# LeaversDinner_invite_Sch.net
KiCad netlist of a schematic drawn in Altium Designer
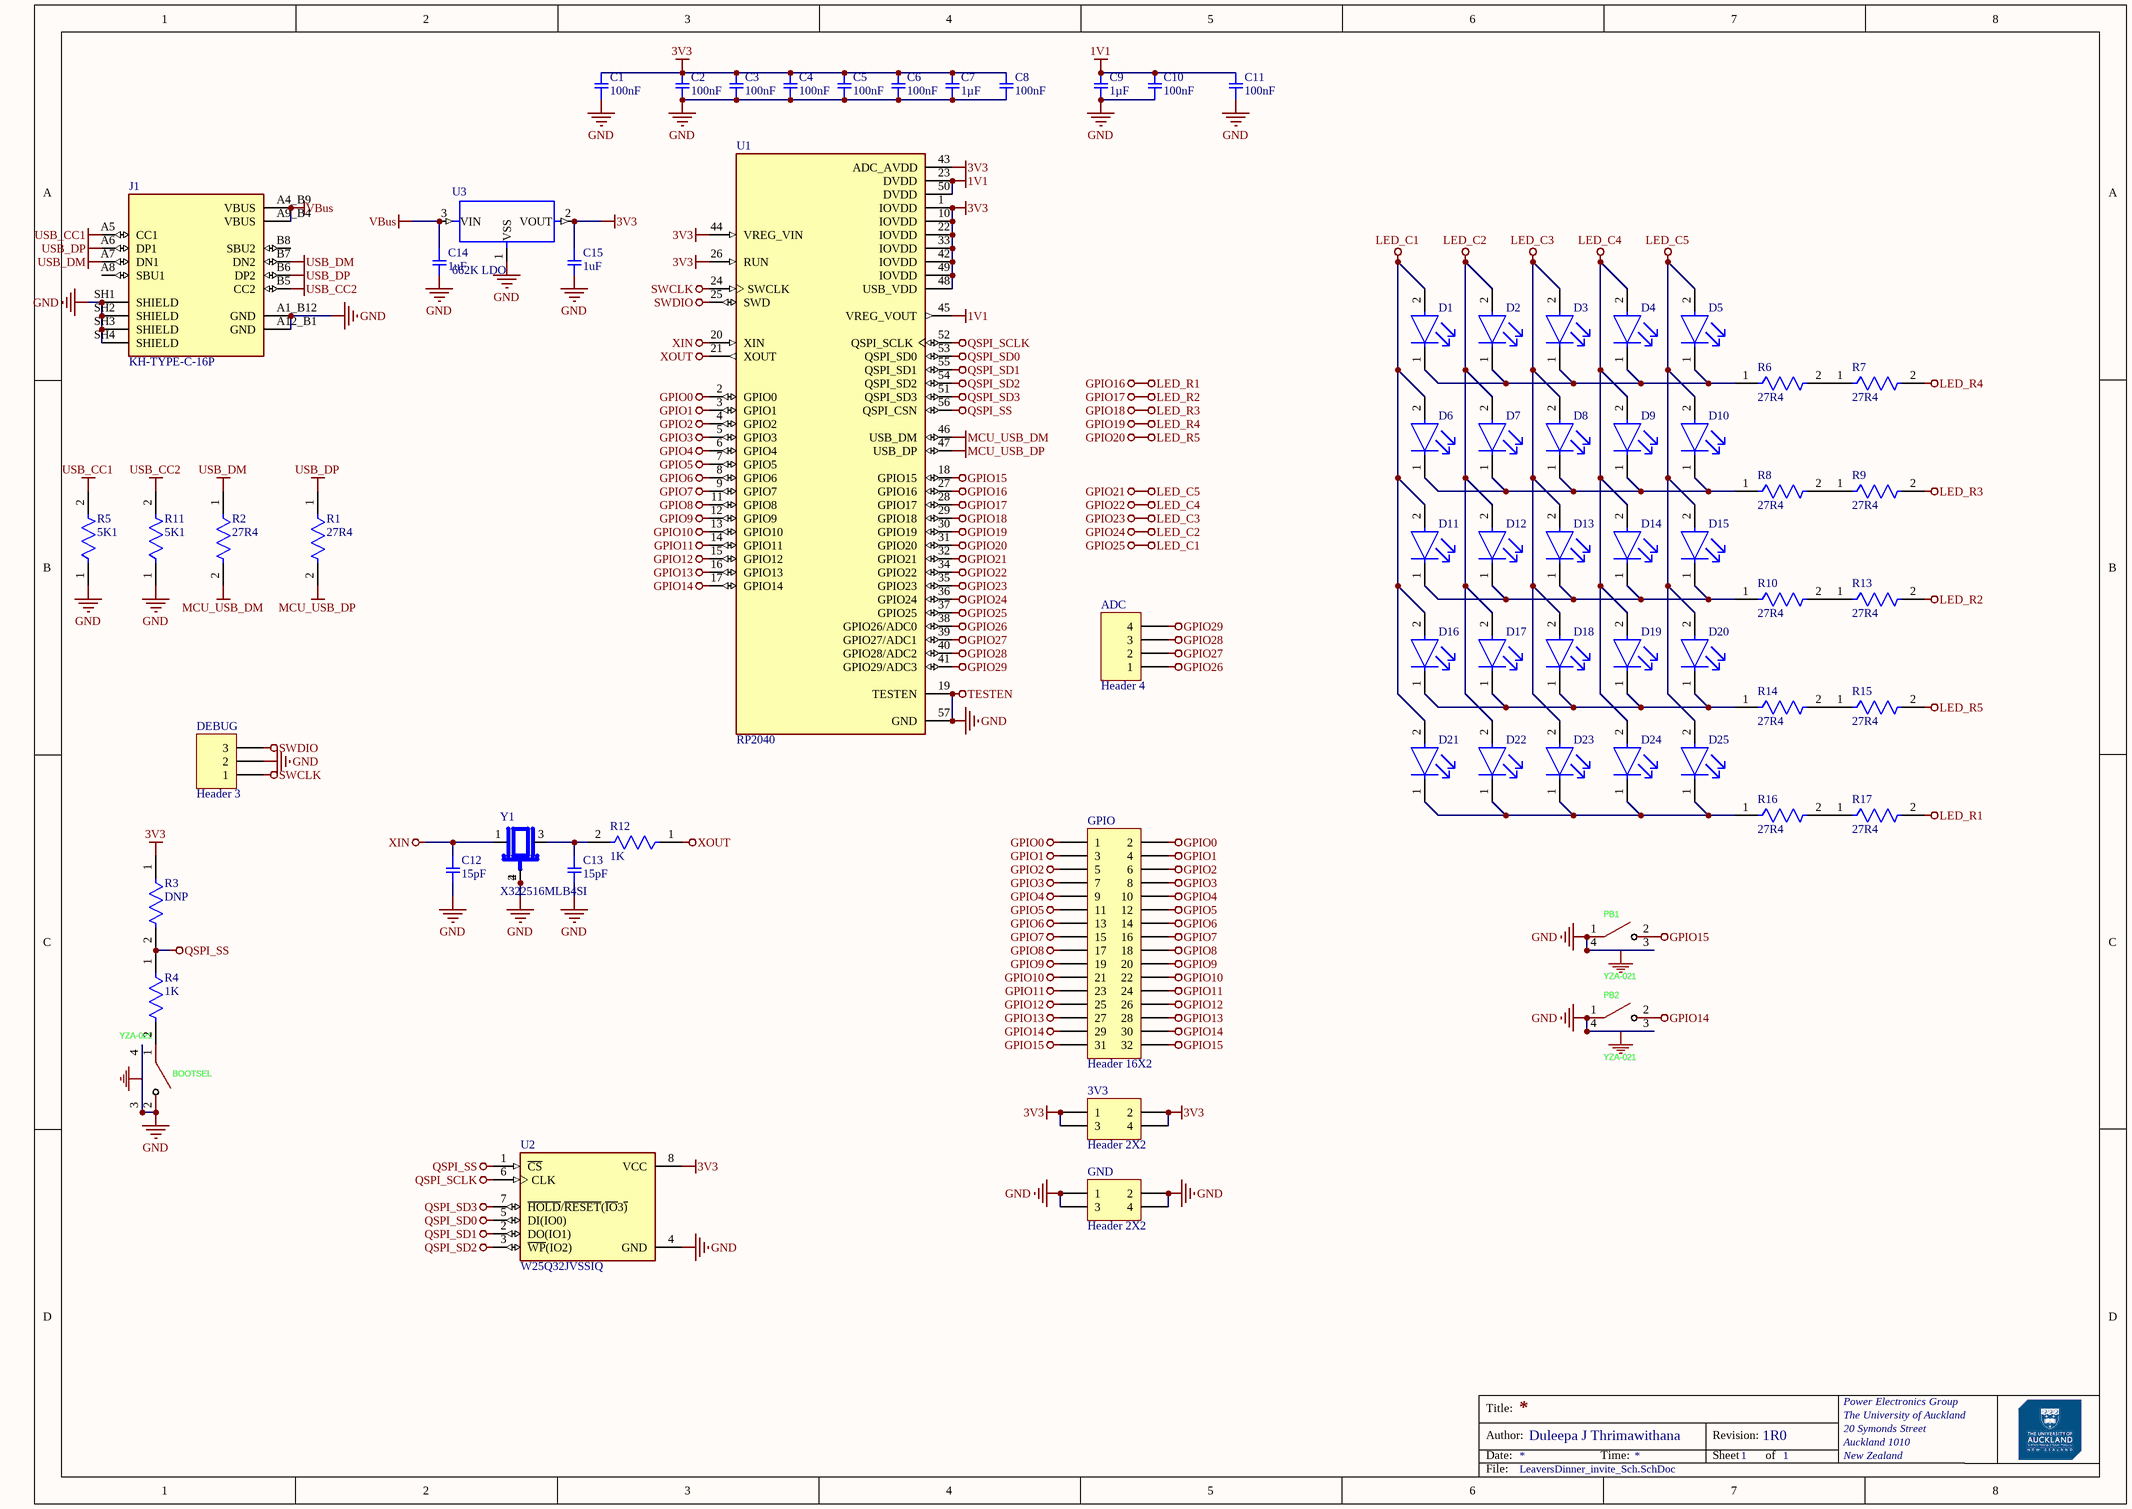
[diagram p0: LeaversDinner_invite_Sch.SchDoc]

(export (version "E")
  (design (tool "Eeschema 10.0.6"))
  (components
    (comp (ref "3V3")
      (value "Header 2X2")
      (footprint "HDR2X2")
      (description "Header, 2-Pin, Dual row")
      (fields (field (name "PUBLISHER") "Altium Limited"))
      (libsource (lib "Miscellaneous Connectors") (part "Header 2X2"))
    )
    (comp (ref "ADC")
      (value "Header 4")
      (footprint "HDR1X4")
      (description "Header, 4-Pin")
      (fields (field (name "PUBLISHER") "Altium Limited"))
      (libsource (lib "Miscellaneous Connectors") (part "Header 4"))
    )
    (comp (ref "BOOTSEL")
      (value "YZA-021")
      (footprint "SW-SMD_YZA-021")
      (fields (field (name "MANUFACTURER") "YIZHI(逸致)"))
      (libsource (lib "YZA-021") (part "YZA-021"))
    )
    (comp (ref "C1")
      (value "100nF")
      (footprint "SMD-0402C")
      (description "CAP CER 1UF 10V X7S 0402")
      (fields
        (field (name "DIGI-KEY PART NUMBER") "490-13409-1-ND")
        (field (name "PART NUMBER") "GCM155C71A105KE38D")
      )
      (libsource (lib "capacitor_murata_0402") (part "GCM155C71A105KE38D"))
    )
    (comp (ref "C2")
      (value "100nF")
      (footprint "SMD-0402C")
      (description "CAP CER 1UF 10V X7S 0402")
      (fields
        (field (name "DIGI-KEY PART NUMBER") "490-13409-1-ND")
        (field (name "PART NUMBER") "GCM155C71A105KE38D")
      )
      (libsource (lib "capacitor_murata_0402") (part "GCM155C71A105KE38D"))
    )
    (comp (ref "C3")
      (value "100nF")
      (footprint "SMD-0402C")
      (description "CAP CER 1UF 10V X7S 0402")
      (fields
        (field (name "DIGI-KEY PART NUMBER") "490-13409-1-ND")
        (field (name "PART NUMBER") "GCM155C71A105KE38D")
      )
      (libsource (lib "capacitor_murata_0402") (part "GCM155C71A105KE38D"))
    )
    (comp (ref "C4")
      (value "100nF")
      (footprint "SMD-0402C")
      (description "CAP CER 1UF 10V X7S 0402")
      (fields
        (field (name "DIGI-KEY PART NUMBER") "490-13409-1-ND")
        (field (name "PART NUMBER") "GCM155C71A105KE38D")
      )
      (libsource (lib "capacitor_murata_0402") (part "GCM155C71A105KE38D"))
    )
    (comp (ref "C5")
      (value "100nF")
      (footprint "SMD-0402C")
      (description "CAP CER 1UF 10V X7S 0402")
      (fields
        (field (name "DIGI-KEY PART NUMBER") "490-13409-1-ND")
        (field (name "PART NUMBER") "GCM155C71A105KE38D")
      )
      (libsource (lib "capacitor_murata_0402") (part "GCM155C71A105KE38D"))
    )
    (comp (ref "C6")
      (value "100nF")
      (footprint "SMD-0402C")
      (description "CAP CER 1UF 10V X7S 0402")
      (fields
        (field (name "DIGI-KEY PART NUMBER") "490-13409-1-ND")
        (field (name "PART NUMBER") "GCM155C71A105KE38D")
      )
      (libsource (lib "capacitor_murata_0402") (part "GCM155C71A105KE38D"))
    )
    (comp (ref "C7")
      (value "1µF")
      (footprint "SMD-0402C")
      (description "CAP CER 1UF 10V X7S 0402")
      (fields
        (field (name "DIGI-KEY PART NUMBER") "490-13409-1-ND")
        (field (name "PART NUMBER") "GCM155C71A105KE38D")
      )
      (libsource (lib "capacitor_murata_0402") (part "GCM155C71A105KE38D"))
    )
    (comp (ref "C8")
      (value "100nF")
      (footprint "SMD-0402C")
      (description "CAP CER 1UF 10V X7S 0402")
      (fields
        (field (name "DIGI-KEY PART NUMBER") "490-13409-1-ND")
        (field (name "PART NUMBER") "GCM155C71A105KE38D")
      )
      (libsource (lib "capacitor_murata_0402") (part "GCM155C71A105KE38D"))
    )
    (comp (ref "C9")
      (value "1µF")
      (footprint "SMD-0402C")
      (description "CAP CER 1UF 10V X7S 0402")
      (fields
        (field (name "DIGI-KEY PART NUMBER") "490-13409-1-ND")
        (field (name "PART NUMBER") "GCM155C71A105KE38D")
      )
      (libsource (lib "capacitor_murata_0402") (part "GCM155C71A105KE38D"))
    )
    (comp (ref "C10")
      (value "100nF")
      (footprint "SMD-0402C")
      (description "CAP CER 1UF 10V X7S 0402")
      (fields
        (field (name "DIGI-KEY PART NUMBER") "490-13409-1-ND")
        (field (name "PART NUMBER") "GCM155C71A105KE38D")
      )
      (libsource (lib "capacitor_murata_0402") (part "GCM155C71A105KE38D"))
    )
    (comp (ref "C11")
      (value "100nF")
      (footprint "SMD-0402C")
      (description "CAP CER 1UF 10V X7S 0402")
      (fields
        (field (name "DIGI-KEY PART NUMBER") "490-13409-1-ND")
        (field (name "PART NUMBER") "GCM155C71A105KE38D")
      )
      (libsource (lib "capacitor_murata_0402") (part "GCM155C71A105KE38D"))
    )
    (comp (ref "C12")
      (value "15pF")
      (footprint "SMD-0402C")
      (description "CAP CER 1UF 10V X7S 0402")
      (fields
        (field (name "DIGI-KEY PART NUMBER") "490-13409-1-ND")
        (field (name "PART NUMBER") "GCM155C71A105KE38D")
      )
      (libsource (lib "capacitor_murata_0402") (part "GCM155C71A105KE38D"))
    )
    (comp (ref "C13")
      (value "15pF")
      (footprint "SMD-0402C")
      (description "CAP CER 1UF 10V X7S 0402")
      (fields
        (field (name "DIGI-KEY PART NUMBER") "490-13409-1-ND")
        (field (name "PART NUMBER") "GCM155C71A105KE38D")
      )
      (libsource (lib "capacitor_murata_0402") (part "GCM155C71A105KE38D"))
    )
    (comp (ref "C14")
      (value "1uF")
      (footprint "SMD-0402C")
      (description "CAP CER 1UF 10V X7S 0402")
      (fields
        (field (name "DIGI-KEY PART NUMBER") "490-13409-1-ND")
        (field (name "PART NUMBER") "GCM155C71A105KE38D")
      )
      (libsource (lib "capacitor_murata_0402") (part "GCM155C71A105KE38D"))
    )
    (comp (ref "C15")
      (value "1uF")
      (footprint "SMD-0402C")
      (description "CAP CER 1UF 10V X7S 0402")
      (fields
        (field (name "DIGI-KEY PART NUMBER") "490-13409-1-ND")
        (field (name "PART NUMBER") "GCM155C71A105KE38D")
      )
      (libsource (lib "capacitor_murata_0402") (part "GCM155C71A105KE38D"))
    )
    (comp (ref "D1")
      (value "VLMW1300-GS08")
      (footprint "FP-6_541-5091_01-4-MFG")
      (description "LED COOL WHITE 0603 SMD")
      (fields
        (field (name "MANUFACTURER") "Vishay")
        (field (name "OCTOPART") "https://octopart.com/vlmw1300-gs08-vishay-21709203")
      )
      (libsource (lib "Altium Content Vault") (part "8706943c75ba83719d021d2fdc84c58"))
    )
    (comp (ref "D2")
      (value "VLMW1300-GS08")
      (footprint "FP-6_541-5091_01-4-MFG")
      (description "LED COOL WHITE 0603 SMD")
      (fields
        (field (name "MANUFACTURER") "Vishay")
        (field (name "OCTOPART") "https://octopart.com/vlmw1300-gs08-vishay-21709203")
      )
      (libsource (lib "Altium Content Vault") (part "8706943c75ba83719d021d2fdc84c58"))
    )
    (comp (ref "D3")
      (value "VLMW1300-GS08")
      (footprint "FP-6_541-5091_01-4-MFG")
      (description "LED COOL WHITE 0603 SMD")
      (fields
        (field (name "MANUFACTURER") "Vishay")
        (field (name "OCTOPART") "https://octopart.com/vlmw1300-gs08-vishay-21709203")
      )
      (libsource (lib "Altium Content Vault") (part "8706943c75ba83719d021d2fdc84c58"))
    )
    (comp (ref "D4")
      (value "VLMW1300-GS08")
      (footprint "FP-6_541-5091_01-4-MFG")
      (description "LED COOL WHITE 0603 SMD")
      (fields
        (field (name "MANUFACTURER") "Vishay")
        (field (name "OCTOPART") "https://octopart.com/vlmw1300-gs08-vishay-21709203")
      )
      (libsource (lib "Altium Content Vault") (part "8706943c75ba83719d021d2fdc84c58"))
    )
    (comp (ref "D5")
      (value "VLMW1300-GS08")
      (footprint "FP-6_541-5091_01-4-MFG")
      (description "LED COOL WHITE 0603 SMD")
      (fields
        (field (name "MANUFACTURER") "Vishay")
        (field (name "OCTOPART") "https://octopart.com/vlmw1300-gs08-vishay-21709203")
      )
      (libsource (lib "Altium Content Vault") (part "8706943c75ba83719d021d2fdc84c58"))
    )
    (comp (ref "D6")
      (value "VLMW1300-GS08")
      (footprint "FP-6_541-5091_01-4-MFG")
      (description "LED COOL WHITE 0603 SMD")
      (fields
        (field (name "MANUFACTURER") "Vishay")
        (field (name "OCTOPART") "https://octopart.com/vlmw1300-gs08-vishay-21709203")
      )
      (libsource (lib "Altium Content Vault") (part "8706943c75ba83719d021d2fdc84c58"))
    )
    (comp (ref "D7")
      (value "VLMW1300-GS08")
      (footprint "FP-6_541-5091_01-4-MFG")
      (description "LED COOL WHITE 0603 SMD")
      (fields
        (field (name "MANUFACTURER") "Vishay")
        (field (name "OCTOPART") "https://octopart.com/vlmw1300-gs08-vishay-21709203")
      )
      (libsource (lib "Altium Content Vault") (part "8706943c75ba83719d021d2fdc84c58"))
    )
    (comp (ref "D8")
      (value "VLMW1300-GS08")
      (footprint "FP-6_541-5091_01-4-MFG")
      (description "LED COOL WHITE 0603 SMD")
      (fields
        (field (name "MANUFACTURER") "Vishay")
        (field (name "OCTOPART") "https://octopart.com/vlmw1300-gs08-vishay-21709203")
      )
      (libsource (lib "Altium Content Vault") (part "8706943c75ba83719d021d2fdc84c58"))
    )
    (comp (ref "D9")
      (value "VLMW1300-GS08")
      (footprint "FP-6_541-5091_01-4-MFG")
      (description "LED COOL WHITE 0603 SMD")
      (fields
        (field (name "MANUFACTURER") "Vishay")
        (field (name "OCTOPART") "https://octopart.com/vlmw1300-gs08-vishay-21709203")
      )
      (libsource (lib "Altium Content Vault") (part "8706943c75ba83719d021d2fdc84c58"))
    )
    (comp (ref "D10")
      (value "VLMW1300-GS08")
      (footprint "FP-6_541-5091_01-4-MFG")
      (description "LED COOL WHITE 0603 SMD")
      (fields
        (field (name "MANUFACTURER") "Vishay")
        (field (name "OCTOPART") "https://octopart.com/vlmw1300-gs08-vishay-21709203")
      )
      (libsource (lib "Altium Content Vault") (part "8706943c75ba83719d021d2fdc84c58"))
    )
    (comp (ref "D11")
      (value "VLMW1300-GS08")
      (footprint "FP-6_541-5091_01-4-MFG")
      (description "LED COOL WHITE 0603 SMD")
      (fields
        (field (name "MANUFACTURER") "Vishay")
        (field (name "OCTOPART") "https://octopart.com/vlmw1300-gs08-vishay-21709203")
      )
      (libsource (lib "Altium Content Vault") (part "8706943c75ba83719d021d2fdc84c58"))
    )
    (comp (ref "D12")
      (value "VLMW1300-GS08")
      (footprint "FP-6_541-5091_01-4-MFG")
      (description "LED COOL WHITE 0603 SMD")
      (fields
        (field (name "MANUFACTURER") "Vishay")
        (field (name "OCTOPART") "https://octopart.com/vlmw1300-gs08-vishay-21709203")
      )
      (libsource (lib "Altium Content Vault") (part "8706943c75ba83719d021d2fdc84c58"))
    )
    (comp (ref "D13")
      (value "VLMW1300-GS08")
      (footprint "FP-6_541-5091_01-4-MFG")
      (description "LED COOL WHITE 0603 SMD")
      (fields
        (field (name "MANUFACTURER") "Vishay")
        (field (name "OCTOPART") "https://octopart.com/vlmw1300-gs08-vishay-21709203")
      )
      (libsource (lib "Altium Content Vault") (part "8706943c75ba83719d021d2fdc84c58"))
    )
    (comp (ref "D14")
      (value "VLMW1300-GS08")
      (footprint "FP-6_541-5091_01-4-MFG")
      (description "LED COOL WHITE 0603 SMD")
      (fields
        (field (name "MANUFACTURER") "Vishay")
        (field (name "OCTOPART") "https://octopart.com/vlmw1300-gs08-vishay-21709203")
      )
      (libsource (lib "Altium Content Vault") (part "8706943c75ba83719d021d2fdc84c58"))
    )
    (comp (ref "D15")
      (value "VLMW1300-GS08")
      (footprint "FP-6_541-5091_01-4-MFG")
      (description "LED COOL WHITE 0603 SMD")
      (fields
        (field (name "MANUFACTURER") "Vishay")
        (field (name "OCTOPART") "https://octopart.com/vlmw1300-gs08-vishay-21709203")
      )
      (libsource (lib "Altium Content Vault") (part "8706943c75ba83719d021d2fdc84c58"))
    )
    (comp (ref "D16")
      (value "VLMW1300-GS08")
      (footprint "FP-6_541-5091_01-4-MFG")
      (description "LED COOL WHITE 0603 SMD")
      (fields
        (field (name "MANUFACTURER") "Vishay")
        (field (name "OCTOPART") "https://octopart.com/vlmw1300-gs08-vishay-21709203")
      )
      (libsource (lib "Altium Content Vault") (part "8706943c75ba83719d021d2fdc84c58"))
    )
    (comp (ref "D17")
      (value "VLMW1300-GS08")
      (footprint "FP-6_541-5091_01-4-MFG")
      (description "LED COOL WHITE 0603 SMD")
      (fields
        (field (name "MANUFACTURER") "Vishay")
        (field (name "OCTOPART") "https://octopart.com/vlmw1300-gs08-vishay-21709203")
      )
      (libsource (lib "Altium Content Vault") (part "8706943c75ba83719d021d2fdc84c58"))
    )
    (comp (ref "D18")
      (value "VLMW1300-GS08")
      (footprint "FP-6_541-5091_01-4-MFG")
      (description "LED COOL WHITE 0603 SMD")
      (fields
        (field (name "MANUFACTURER") "Vishay")
        (field (name "OCTOPART") "https://octopart.com/vlmw1300-gs08-vishay-21709203")
      )
      (libsource (lib "Altium Content Vault") (part "8706943c75ba83719d021d2fdc84c58"))
    )
    (comp (ref "D19")
      (value "VLMW1300-GS08")
      (footprint "FP-6_541-5091_01-4-MFG")
      (description "LED COOL WHITE 0603 SMD")
      (fields
        (field (name "MANUFACTURER") "Vishay")
        (field (name "OCTOPART") "https://octopart.com/vlmw1300-gs08-vishay-21709203")
      )
      (libsource (lib "Altium Content Vault") (part "8706943c75ba83719d021d2fdc84c58"))
    )
    (comp (ref "D20")
      (value "VLMW1300-GS08")
      (footprint "FP-6_541-5091_01-4-MFG")
      (description "LED COOL WHITE 0603 SMD")
      (fields
        (field (name "MANUFACTURER") "Vishay")
        (field (name "OCTOPART") "https://octopart.com/vlmw1300-gs08-vishay-21709203")
      )
      (libsource (lib "Altium Content Vault") (part "8706943c75ba83719d021d2fdc84c58"))
    )
    (comp (ref "D21")
      (value "VLMW1300-GS08")
      (footprint "FP-6_541-5091_01-4-MFG")
      (description "LED COOL WHITE 0603 SMD")
      (fields
        (field (name "MANUFACTURER") "Vishay")
        (field (name "OCTOPART") "https://octopart.com/vlmw1300-gs08-vishay-21709203")
      )
      (libsource (lib "Altium Content Vault") (part "8706943c75ba83719d021d2fdc84c58"))
    )
    (comp (ref "D22")
      (value "VLMW1300-GS08")
      (footprint "FP-6_541-5091_01-4-MFG")
      (description "LED COOL WHITE 0603 SMD")
      (fields
        (field (name "MANUFACTURER") "Vishay")
        (field (name "OCTOPART") "https://octopart.com/vlmw1300-gs08-vishay-21709203")
      )
      (libsource (lib "Altium Content Vault") (part "8706943c75ba83719d021d2fdc84c58"))
    )
    (comp (ref "D23")
      (value "VLMW1300-GS08")
      (footprint "FP-6_541-5091_01-4-MFG")
      (description "LED COOL WHITE 0603 SMD")
      (fields
        (field (name "MANUFACTURER") "Vishay")
        (field (name "OCTOPART") "https://octopart.com/vlmw1300-gs08-vishay-21709203")
      )
      (libsource (lib "Altium Content Vault") (part "8706943c75ba83719d021d2fdc84c58"))
    )
    (comp (ref "D24")
      (value "VLMW1300-GS08")
      (footprint "FP-6_541-5091_01-4-MFG")
      (description "LED COOL WHITE 0603 SMD")
      (fields
        (field (name "MANUFACTURER") "Vishay")
        (field (name "OCTOPART") "https://octopart.com/vlmw1300-gs08-vishay-21709203")
      )
      (libsource (lib "Altium Content Vault") (part "8706943c75ba83719d021d2fdc84c58"))
    )
    (comp (ref "D25")
      (value "VLMW1300-GS08")
      (footprint "FP-6_541-5091_01-4-MFG")
      (description "LED COOL WHITE 0603 SMD")
      (fields
        (field (name "MANUFACTURER") "Vishay")
        (field (name "OCTOPART") "https://octopart.com/vlmw1300-gs08-vishay-21709203")
      )
      (libsource (lib "Altium Content Vault") (part "8706943c75ba83719d021d2fdc84c58"))
    )
    (comp (ref "DEBUG")
      (value "Header 3")
      (footprint "HDR1X3")
      (description "Header, 3-Pin")
      (fields (field (name "PUBLISHER") "Altium Limited"))
      (libsource (lib "Miscellaneous Connectors") (part "Header 3"))
    )
    (comp (ref "GND")
      (value "Header 2X2")
      (footprint "HDR2X2")
      (description "Header, 2-Pin, Dual row")
      (fields (field (name "PUBLISHER") "Altium Limited"))
      (libsource (lib "Miscellaneous Connectors") (part "Header 2X2"))
    )
    (comp (ref "GPIO")
      (value "Header 16X2")
      (footprint "HDR2X16")
      (description "Header, 16-Pin, Dual row")
      (fields (field (name "PUBLISHER") "Altium Limited"))
      (libsource (lib "Miscellaneous Connectors") (part "Header 16X2"))
    )
    (comp (ref "J1")
      (value "KH-TYPE-C-16P")
      (footprint "KINGHELM_KH-TYPE-C-16P")
      (fields (field (name "MF") "kinghelm"))
      (libsource (lib "KH-TYPE-C-16P") (part "KH-TYPE-C-16P"))
    )
    (comp (ref "PB1")
      (value "YZA-021")
      (footprint "SW-SMD_YZA-021")
      (fields (field (name "MANUFACTURER") "YIZHI(逸致)"))
      (libsource (lib "YZA-021") (part "YZA-021"))
    )
    (comp (ref "PB2")
      (value "YZA-021")
      (footprint "SW-SMD_YZA-021")
      (fields (field (name "MANUFACTURER") "YIZHI(逸致)"))
      (libsource (lib "YZA-021") (part "YZA-021"))
    )
    (comp (ref "R1")
      (value "27R4")
      (footprint "FP-MCR01-IPC_B")
      (description "Thick Film Chip Resistor, 0402, 10MΩ, 5%, 200ppm/°C, 0.063W, 50V")
      (fields (field (name "TOLERANCE") "5%"))
      (libsource (lib "Altium Content Vault") (part "1029c3af85768c4190bb7ad29bc67b5"))
    )
    (comp (ref "R2")
      (value "27R4")
      (footprint "FP-MCR01-IPC_B")
      (description "Thick Film Chip Resistor, 0402, 10MΩ, 5%, 200ppm/°C, 0.063W, 50V")
      (fields (field (name "TOLERANCE") "5%"))
      (libsource (lib "Altium Content Vault") (part "1029c3af85768c4190bb7ad29bc67b5"))
    )
    (comp (ref "R3")
      (value "DNP")
      (footprint "FP-MCR01-IPC_B")
      (description "Thick Film Chip Resistor, 0402, 10MΩ, 5%, 200ppm/°C, 0.063W, 50V")
      (fields (field (name "TOLERANCE") "5%"))
      (libsource (lib "Altium Content Vault") (part "1029c3af85768c4190bb7ad29bc67b5"))
    )
    (comp (ref "R4")
      (value "1K")
      (footprint "FP-MCR01-IPC_B")
      (description "Thick Film Chip Resistor, 0402, 10MΩ, 5%, 200ppm/°C, 0.063W, 50V")
      (fields (field (name "TOLERANCE") "5%"))
      (libsource (lib "Altium Content Vault") (part "1029c3af85768c4190bb7ad29bc67b5"))
    )
    (comp (ref "R5")
      (value "5K1")
      (footprint "FP-MCR01-IPC_B")
      (description "Thick Film Chip Resistor, 0402, 10MΩ, 5%, 200ppm/°C, 0.063W, 50V")
      (fields (field (name "TOLERANCE") "5%"))
      (libsource (lib "Altium Content Vault") (part "1029c3af85768c4190bb7ad29bc67b5"))
    )
    (comp (ref "R6")
      (value "27R4")
      (footprint "FP-MCR01-IPC_B")
      (description "Thick Film Chip Resistor, 0402, 10MΩ, 5%, 200ppm/°C, 0.063W, 50V")
      (fields (field (name "TOLERANCE") "5%"))
      (libsource (lib "Altium Content Vault") (part "1029c3af85768c4190bb7ad29bc67b5"))
    )
    (comp (ref "R7")
      (value "27R4")
      (footprint "FP-MCR01-IPC_B")
      (description "Thick Film Chip Resistor, 0402, 10MΩ, 5%, 200ppm/°C, 0.063W, 50V")
      (fields (field (name "TOLERANCE") "5%"))
      (libsource (lib "Altium Content Vault") (part "1029c3af85768c4190bb7ad29bc67b5"))
    )
    (comp (ref "R8")
      (value "27R4")
      (footprint "FP-MCR01-IPC_B")
      (description "Thick Film Chip Resistor, 0402, 10MΩ, 5%, 200ppm/°C, 0.063W, 50V")
      (fields (field (name "TOLERANCE") "5%"))
      (libsource (lib "Altium Content Vault") (part "1029c3af85768c4190bb7ad29bc67b5"))
    )
    (comp (ref "R9")
      (value "27R4")
      (footprint "FP-MCR01-IPC_B")
      (description "Thick Film Chip Resistor, 0402, 10MΩ, 5%, 200ppm/°C, 0.063W, 50V")
      (fields (field (name "TOLERANCE") "5%"))
      (libsource (lib "Altium Content Vault") (part "1029c3af85768c4190bb7ad29bc67b5"))
    )
    (comp (ref "R10")
      (value "27R4")
      (footprint "FP-MCR01-IPC_B")
      (description "Thick Film Chip Resistor, 0402, 10MΩ, 5%, 200ppm/°C, 0.063W, 50V")
      (fields (field (name "TOLERANCE") "5%"))
      (libsource (lib "Altium Content Vault") (part "1029c3af85768c4190bb7ad29bc67b5"))
    )
    (comp (ref "R11")
      (value "5K1")
      (footprint "FP-MCR01-IPC_B")
      (description "Thick Film Chip Resistor, 0402, 10MΩ, 5%, 200ppm/°C, 0.063W, 50V")
      (fields (field (name "TOLERANCE") "5%"))
      (libsource (lib "Altium Content Vault") (part "1029c3af85768c4190bb7ad29bc67b5"))
    )
    (comp (ref "R12")
      (value "1K")
      (footprint "FP-MCR01-IPC_B")
      (description "Thick Film Chip Resistor, 0402, 10MΩ, 5%, 200ppm/°C, 0.063W, 50V")
      (fields (field (name "TOLERANCE") "5%"))
      (libsource (lib "Altium Content Vault") (part "1029c3af85768c4190bb7ad29bc67b5"))
    )
    (comp (ref "R13")
      (value "27R4")
      (footprint "FP-MCR01-IPC_B")
      (description "Thick Film Chip Resistor, 0402, 10MΩ, 5%, 200ppm/°C, 0.063W, 50V")
      (fields (field (name "TOLERANCE") "5%"))
      (libsource (lib "Altium Content Vault") (part "1029c3af85768c4190bb7ad29bc67b5"))
    )
    (comp (ref "R14")
      (value "27R4")
      (footprint "FP-MCR01-IPC_B")
      (description "Thick Film Chip Resistor, 0402, 10MΩ, 5%, 200ppm/°C, 0.063W, 50V")
      (fields (field (name "TOLERANCE") "5%"))
      (libsource (lib "Altium Content Vault") (part "1029c3af85768c4190bb7ad29bc67b5"))
    )
    (comp (ref "R15")
      (value "27R4")
      (footprint "FP-MCR01-IPC_B")
      (description "Thick Film Chip Resistor, 0402, 10MΩ, 5%, 200ppm/°C, 0.063W, 50V")
      (fields (field (name "TOLERANCE") "5%"))
      (libsource (lib "Altium Content Vault") (part "1029c3af85768c4190bb7ad29bc67b5"))
    )
    (comp (ref "R16")
      (value "27R4")
      (footprint "FP-MCR01-IPC_B")
      (description "Thick Film Chip Resistor, 0402, 10MΩ, 5%, 200ppm/°C, 0.063W, 50V")
      (fields (field (name "TOLERANCE") "5%"))
      (libsource (lib "Altium Content Vault") (part "1029c3af85768c4190bb7ad29bc67b5"))
    )
    (comp (ref "R17")
      (value "27R4")
      (footprint "FP-MCR01-IPC_B")
      (description "Thick Film Chip Resistor, 0402, 10MΩ, 5%, 200ppm/°C, 0.063W, 50V")
      (fields (field (name "TOLERANCE") "5%"))
      (libsource (lib "Altium Content Vault") (part "1029c3af85768c4190bb7ad29bc67b5"))
    )
    (comp (ref "U1")
      (value "RP2040")
      (footprint "QFN40P700X700X90-57N")
      (description "RP2040 chip for Raspberry Pi Pico - ARM® Cortex®-M0+ MCU 32-Bit")
      (fields (field (name "MF") "Raspberry Pi"))
      (libsource (lib "RP2040") (part "RP2040"))
    )
    (comp (ref "U2")
      (value "W25Q32JVSSIQ")
      (footprint "SOIC127P790X216-8N")
      (description "FLASH - NOR Memory IC 32Mb (4M x 8) SPI - Quad I/O 133 MHz 8-SOIC")
      (fields (field (name "MF") "Winbond"))
      (libsource (lib "W25Q32JVSSIQ") (part "W25Q32JVSSIQ"))
    )
    (comp (ref "U3")
      (value "662K LDO")
      (footprint "SOT-23")
      (description "Linear Voltage Regulator IC Positive Fixed 1 Output 300mA SOT-23")
      (fields (field (name "MF") "Torex") (field (name "MP") "XC6206P332MR-G"))
      (libsource (lib "PMIC-LDO-XC6206P332MR-G_SOT23_") (part "PMIC-LDO-XC6206P332MR-G(SOT23)"))
    )
    (comp (ref "Y1")
      (value "X322516MLB4SI")
      (footprint "OSC_X322516MLB4SI")
      (description "External dimensions: 3.2 x 2.5 x 0.8 mm.Frequency range: 11.0592MHz ~54MHz")
      (fields (field (name "MF") "YXC"))
      (libsource (lib "X322516MLB4SI") (part "X322516MLB4SI"))
    )
  )
  (nets
    (net (code "1") (name "1V1") (class "Default")
      (node (ref "C10") (pin "2") (pinfunction "2_2") (pintype "passive"))
      (node (ref "C11") (pin "2") (pinfunction "2_2") (pintype "passive"))
      (node (ref "C9") (pin "2") (pinfunction "2_2") (pintype "passive"))
      (node (ref "U1") (pin "23") (pinfunction "DVDD_23") (pintype "power_in"))
      (node (ref "U1") (pin "45") (pinfunction "VREG_VOUT_45") (pintype "output"))
      (node (ref "U1") (pin "50") (pinfunction "DVDD_50") (pintype "power_in"))
    )
    (net (code "2") (name "3V3") (class "Default")
      (node (ref "3V3") (pin "1") (pinfunction "1_1") (pintype "passive"))
      (node (ref "3V3") (pin "2") (pinfunction "2_2") (pintype "passive"))
      (node (ref "3V3") (pin "3") (pinfunction "3_3") (pintype "passive"))
      (node (ref "3V3") (pin "4") (pinfunction "4_4") (pintype "passive"))
      (node (ref "C1") (pin "2") (pinfunction "2_2") (pintype "passive"))
      (node (ref "C15") (pin "1") (pinfunction "1_1") (pintype "passive"))
      (node (ref "C2") (pin "2") (pinfunction "2_2") (pintype "passive"))
      (node (ref "C3") (pin "2") (pinfunction "2_2") (pintype "passive"))
      (node (ref "C4") (pin "2") (pinfunction "2_2") (pintype "passive"))
      (node (ref "C5") (pin "2") (pinfunction "2_2") (pintype "passive"))
      (node (ref "C6") (pin "2") (pinfunction "2_2") (pintype "passive"))
      (node (ref "C7") (pin "2") (pinfunction "2_2") (pintype "passive"))
      (node (ref "C8") (pin "2") (pinfunction "2_2") (pintype "passive"))
      (node (ref "R3") (pin "1") (pinfunction "1_1") (pintype "passive"))
      (node (ref "U1") (pin "1") (pinfunction "IOVDD_1") (pintype "power_in"))
      (node (ref "U1") (pin "10") (pinfunction "IOVDD_10") (pintype "power_in"))
      (node (ref "U1") (pin "22") (pinfunction "IOVDD_22") (pintype "power_in"))
      (node (ref "U1") (pin "26") (pinfunction "RUN_26") (pintype "input"))
      (node (ref "U1") (pin "33") (pinfunction "IOVDD_33") (pintype "power_in"))
      (node (ref "U1") (pin "42") (pinfunction "IOVDD_42") (pintype "power_in"))
      (node (ref "U1") (pin "43") (pinfunction "ADC_AVDD_43") (pintype "power_in"))
      (node (ref "U1") (pin "44") (pinfunction "VREG_VIN_44") (pintype "input"))
      (node (ref "U1") (pin "48") (pinfunction "USB_VDD_48") (pintype "power_in"))
      (node (ref "U1") (pin "49") (pinfunction "IOVDD_49") (pintype "power_in"))
      (node (ref "U2") (pin "8") (pinfunction "VCC_8") (pintype "power_in"))
      (node (ref "U3") (pin "2") (pinfunction "VOUT_2") (pintype "output"))
    )
    (net (code "3") (name "GND") (class "Default")
      (node (ref "BOOTSEL") (pin "2") (pinfunction "2_2") (pintype "passive"))
      (node (ref "BOOTSEL") (pin "3") (pinfunction "3_3") (pintype "passive"))
      (node (ref "BOOTSEL") (pin "4") (pinfunction "4_4") (pintype "passive"))
      (node (ref "C1") (pin "1") (pinfunction "1_1") (pintype "passive"))
      (node (ref "C10") (pin "1") (pinfunction "1_1") (pintype "passive"))
      (node (ref "C11") (pin "1") (pinfunction "1_1") (pintype "passive"))
      (node (ref "C12") (pin "2") (pinfunction "2_2") (pintype "passive"))
      (node (ref "C13") (pin "2") (pinfunction "2_2") (pintype "passive"))
      (node (ref "C14") (pin "2") (pinfunction "2_2") (pintype "passive"))
      (node (ref "C15") (pin "2") (pinfunction "2_2") (pintype "passive"))
      (node (ref "C2") (pin "1") (pinfunction "1_1") (pintype "passive"))
      (node (ref "C3") (pin "1") (pinfunction "1_1") (pintype "passive"))
      (node (ref "C4") (pin "1") (pinfunction "1_1") (pintype "passive"))
      (node (ref "C5") (pin "1") (pinfunction "1_1") (pintype "passive"))
      (node (ref "C6") (pin "1") (pinfunction "1_1") (pintype "passive"))
      (node (ref "C7") (pin "1") (pinfunction "1_1") (pintype "passive"))
      (node (ref "C8") (pin "1") (pinfunction "1_1") (pintype "passive"))
      (node (ref "C9") (pin "1") (pinfunction "1_1") (pintype "passive"))
      (node (ref "DEBUG") (pin "2") (pinfunction "2_2") (pintype "passive"))
      (node (ref "GND") (pin "1") (pinfunction "1_1") (pintype "passive"))
      (node (ref "GND") (pin "2") (pinfunction "2_2") (pintype "passive"))
      (node (ref "GND") (pin "3") (pinfunction "3_3") (pintype "passive"))
      (node (ref "GND") (pin "4") (pinfunction "4_4") (pintype "passive"))
      (node (ref "J1") (pin "A12_B1") (pinfunction "GND_A12_B1") (pintype "power_in"))
      (node (ref "J1") (pin "A1_B12") (pinfunction "GND_A1_B12") (pintype "power_in"))
      (node (ref "J1") (pin "SH1") (pinfunction "SHIELD_SH1") (pintype "passive"))
      (node (ref "J1") (pin "SH2") (pinfunction "SHIELD_SH2") (pintype "passive"))
      (node (ref "J1") (pin "SH3") (pinfunction "SHIELD_SH3") (pintype "passive"))
      (node (ref "J1") (pin "SH4") (pinfunction "SHIELD_SH4") (pintype "passive"))
      (node (ref "PB1") (pin "1") (pinfunction "1_1") (pintype "passive"))
      (node (ref "PB1") (pin "3") (pinfunction "3_3") (pintype "passive"))
      (node (ref "PB1") (pin "4") (pinfunction "4_4") (pintype "passive"))
      (node (ref "PB2") (pin "1") (pinfunction "1_1") (pintype "passive"))
      (node (ref "PB2") (pin "3") (pinfunction "3_3") (pintype "passive"))
      (node (ref "PB2") (pin "4") (pinfunction "4_4") (pintype "passive"))
      (node (ref "R11") (pin "1") (pinfunction "1_1") (pintype "passive"))
      (node (ref "R5") (pin "1") (pinfunction "1_1") (pintype "passive"))
      (node (ref "U1") (pin "19") (pinfunction "TESTEN_19") (pintype "passive"))
      (node (ref "U1") (pin "57") (pinfunction "GND_57") (pintype "power_in"))
      (node (ref "U2") (pin "4") (pinfunction "GND_4") (pintype "power_in"))
      (node (ref "U3") (pin "1") (pinfunction "VSS_1") (pintype "power_in"))
      (node (ref "Y1") (pin "2") (pinfunction "GND_2") (pintype "power_in"))
      (node (ref "Y1") (pin "4") (pinfunction "GND_4") (pintype "power_in"))
    )
    (net (code "4") (name "GPIO0") (class "Default")
      (node (ref "GPIO") (pin "1") (pinfunction "1_1") (pintype "passive"))
      (node (ref "GPIO") (pin "2") (pinfunction "2_2") (pintype "passive"))
      (node (ref "U1") (pin "2") (pinfunction "GPIO0_2") (pintype "bidirectional"))
    )
    (net (code "5") (name "GPIO1") (class "Default")
      (node (ref "GPIO") (pin "3") (pinfunction "3_3") (pintype "passive"))
      (node (ref "GPIO") (pin "4") (pinfunction "4_4") (pintype "passive"))
      (node (ref "U1") (pin "3") (pinfunction "GPIO1_3") (pintype "bidirectional"))
    )
    (net (code "6") (name "GPIO2") (class "Default")
      (node (ref "GPIO") (pin "5") (pinfunction "5_5") (pintype "passive"))
      (node (ref "GPIO") (pin "6") (pinfunction "6_6") (pintype "passive"))
      (node (ref "U1") (pin "4") (pinfunction "GPIO2_4") (pintype "bidirectional"))
    )
    (net (code "7") (name "GPIO3") (class "Default")
      (node (ref "GPIO") (pin "7") (pinfunction "7_7") (pintype "passive"))
      (node (ref "GPIO") (pin "8") (pinfunction "8_8") (pintype "passive"))
      (node (ref "U1") (pin "5") (pinfunction "GPIO3_5") (pintype "bidirectional"))
    )
    (net (code "8") (name "GPIO4") (class "Default")
      (node (ref "GPIO") (pin "10") (pinfunction "10_10") (pintype "passive"))
      (node (ref "GPIO") (pin "9") (pinfunction "9_9") (pintype "passive"))
      (node (ref "U1") (pin "6") (pinfunction "GPIO4_6") (pintype "bidirectional"))
    )
    (net (code "9") (name "GPIO5") (class "Default")
      (node (ref "GPIO") (pin "11") (pinfunction "11_11") (pintype "passive"))
      (node (ref "GPIO") (pin "12") (pinfunction "12_12") (pintype "passive"))
      (node (ref "U1") (pin "7") (pinfunction "GPIO5_7") (pintype "bidirectional"))
    )
    (net (code "10") (name "GPIO6") (class "Default")
      (node (ref "GPIO") (pin "13") (pinfunction "13_13") (pintype "passive"))
      (node (ref "GPIO") (pin "14") (pinfunction "14_14") (pintype "passive"))
      (node (ref "U1") (pin "8") (pinfunction "GPIO6_8") (pintype "bidirectional"))
    )
    (net (code "11") (name "GPIO7") (class "Default")
      (node (ref "GPIO") (pin "15") (pinfunction "15_15") (pintype "passive"))
      (node (ref "GPIO") (pin "16") (pinfunction "16_16") (pintype "passive"))
      (node (ref "U1") (pin "9") (pinfunction "GPIO7_9") (pintype "bidirectional"))
    )
    (net (code "12") (name "GPIO8") (class "Default")
      (node (ref "GPIO") (pin "17") (pinfunction "17_17") (pintype "passive"))
      (node (ref "GPIO") (pin "18") (pinfunction "18_18") (pintype "passive"))
      (node (ref "U1") (pin "11") (pinfunction "GPIO8_11") (pintype "bidirectional"))
    )
    (net (code "13") (name "GPIO9") (class "Default")
      (node (ref "GPIO") (pin "19") (pinfunction "19_19") (pintype "passive"))
      (node (ref "GPIO") (pin "20") (pinfunction "20_20") (pintype "passive"))
      (node (ref "U1") (pin "12") (pinfunction "GPIO9_12") (pintype "bidirectional"))
    )
    (net (code "14") (name "GPIO10") (class "Default")
      (node (ref "GPIO") (pin "21") (pinfunction "21_21") (pintype "passive"))
      (node (ref "GPIO") (pin "22") (pinfunction "22_22") (pintype "passive"))
      (node (ref "U1") (pin "13") (pinfunction "GPIO10_13") (pintype "bidirectional"))
    )
    (net (code "15") (name "GPIO11") (class "Default")
      (node (ref "GPIO") (pin "23") (pinfunction "23_23") (pintype "passive"))
      (node (ref "GPIO") (pin "24") (pinfunction "24_24") (pintype "passive"))
      (node (ref "U1") (pin "14") (pinfunction "GPIO11_14") (pintype "bidirectional"))
    )
    (net (code "16") (name "GPIO12") (class "Default")
      (node (ref "GPIO") (pin "25") (pinfunction "25_25") (pintype "passive"))
      (node (ref "GPIO") (pin "26") (pinfunction "26_26") (pintype "passive"))
      (node (ref "U1") (pin "15") (pinfunction "GPIO12_15") (pintype "bidirectional"))
    )
    (net (code "17") (name "GPIO13") (class "Default")
      (node (ref "GPIO") (pin "27") (pinfunction "27_27") (pintype "passive"))
      (node (ref "GPIO") (pin "28") (pinfunction "28_28") (pintype "passive"))
      (node (ref "U1") (pin "16") (pinfunction "GPIO13_16") (pintype "bidirectional"))
    )
    (net (code "18") (name "GPIO14") (class "Default")
      (node (ref "GPIO") (pin "29") (pinfunction "29_29") (pintype "passive"))
      (node (ref "GPIO") (pin "30") (pinfunction "30_30") (pintype "passive"))
      (node (ref "PB2") (pin "2") (pinfunction "2_2") (pintype "passive"))
      (node (ref "U1") (pin "17") (pinfunction "GPIO14_17") (pintype "bidirectional"))
    )
    (net (code "19") (name "GPIO15") (class "Default")
      (node (ref "GPIO") (pin "31") (pinfunction "31_31") (pintype "passive"))
      (node (ref "GPIO") (pin "32") (pinfunction "32_32") (pintype "passive"))
      (node (ref "PB1") (pin "2") (pinfunction "2_2") (pintype "passive"))
      (node (ref "U1") (pin "18") (pinfunction "GPIO15_18") (pintype "bidirectional"))
    )
    (net (code "20") (name "GPIO16") (class "Default")
      (node (ref "R17") (pin "2") (pinfunction "2_2") (pintype "passive"))
      (node (ref "U1") (pin "27") (pinfunction "GPIO16_27") (pintype "bidirectional"))
    )
    (net (code "21") (name "GPIO17") (class "Default")
      (node (ref "R13") (pin "2") (pinfunction "2_2") (pintype "passive"))
      (node (ref "U1") (pin "28") (pinfunction "GPIO17_28") (pintype "bidirectional"))
    )
    (net (code "22") (name "GPIO18") (class "Default")
      (node (ref "R9") (pin "2") (pinfunction "2_2") (pintype "passive"))
      (node (ref "U1") (pin "29") (pinfunction "GPIO18_29") (pintype "bidirectional"))
    )
    (net (code "23") (name "GPIO19") (class "Default")
      (node (ref "R7") (pin "2") (pinfunction "2_2") (pintype "passive"))
      (node (ref "U1") (pin "30") (pinfunction "GPIO19_30") (pintype "bidirectional"))
    )
    (net (code "24") (name "GPIO20") (class "Default")
      (node (ref "R15") (pin "2") (pinfunction "2_2") (pintype "passive"))
      (node (ref "U1") (pin "31") (pinfunction "GPIO20_31") (pintype "bidirectional"))
    )
    (net (code "25") (name "GPIO21") (class "Default")
      (node (ref "D10") (pin "2") (pinfunction "A_2") (pintype "passive"))
      (node (ref "D15") (pin "2") (pinfunction "A_2") (pintype "passive"))
      (node (ref "D20") (pin "2") (pinfunction "A_2") (pintype "passive"))
      (node (ref "D25") (pin "2") (pinfunction "A_2") (pintype "passive"))
      (node (ref "D5") (pin "2") (pinfunction "A_2") (pintype "passive"))
      (node (ref "U1") (pin "32") (pinfunction "GPIO21_32") (pintype "bidirectional"))
    )
    (net (code "26") (name "GPIO22") (class "Default")
      (node (ref "D14") (pin "2") (pinfunction "A_2") (pintype "passive"))
      (node (ref "D19") (pin "2") (pinfunction "A_2") (pintype "passive"))
      (node (ref "D24") (pin "2") (pinfunction "A_2") (pintype "passive"))
      (node (ref "D4") (pin "2") (pinfunction "A_2") (pintype "passive"))
      (node (ref "D9") (pin "2") (pinfunction "A_2") (pintype "passive"))
      (node (ref "U1") (pin "34") (pinfunction "GPIO22_34") (pintype "bidirectional"))
    )
    (net (code "27") (name "GPIO23") (class "Default")
      (node (ref "D13") (pin "2") (pinfunction "A_2") (pintype "passive"))
      (node (ref "D18") (pin "2") (pinfunction "A_2") (pintype "passive"))
      (node (ref "D23") (pin "2") (pinfunction "A_2") (pintype "passive"))
      (node (ref "D3") (pin "2") (pinfunction "A_2") (pintype "passive"))
      (node (ref "D8") (pin "2") (pinfunction "A_2") (pintype "passive"))
      (node (ref "U1") (pin "35") (pinfunction "GPIO23_35") (pintype "bidirectional"))
    )
    (net (code "28") (name "GPIO24") (class "Default")
      (node (ref "D12") (pin "2") (pinfunction "A_2") (pintype "passive"))
      (node (ref "D17") (pin "2") (pinfunction "A_2") (pintype "passive"))
      (node (ref "D2") (pin "2") (pinfunction "A_2") (pintype "passive"))
      (node (ref "D22") (pin "2") (pinfunction "A_2") (pintype "passive"))
      (node (ref "D7") (pin "2") (pinfunction "A_2") (pintype "passive"))
      (node (ref "U1") (pin "36") (pinfunction "GPIO24_36") (pintype "bidirectional"))
    )
    (net (code "29") (name "GPIO25") (class "Default")
      (node (ref "D1") (pin "2") (pinfunction "A_2") (pintype "passive"))
      (node (ref "D11") (pin "2") (pinfunction "A_2") (pintype "passive"))
      (node (ref "D16") (pin "2") (pinfunction "A_2") (pintype "passive"))
      (node (ref "D21") (pin "2") (pinfunction "A_2") (pintype "passive"))
      (node (ref "D6") (pin "2") (pinfunction "A_2") (pintype "passive"))
      (node (ref "U1") (pin "37") (pinfunction "GPIO25_37") (pintype "bidirectional"))
    )
    (net (code "30") (name "GPIO26") (class "Default")
      (node (ref "ADC") (pin "1") (pinfunction "1_1") (pintype "passive"))
      (node (ref "U1") (pin "38") (pinfunction "GPIO26/ADC0_38") (pintype "bidirectional"))
    )
    (net (code "31") (name "GPIO27") (class "Default")
      (node (ref "ADC") (pin "2") (pinfunction "2_2") (pintype "passive"))
      (node (ref "U1") (pin "39") (pinfunction "GPIO27/ADC1_39") (pintype "bidirectional"))
    )
    (net (code "32") (name "GPIO28") (class "Default")
      (node (ref "ADC") (pin "3") (pinfunction "3_3") (pintype "passive"))
      (node (ref "U1") (pin "40") (pinfunction "GPIO28/ADC2_40") (pintype "bidirectional"))
    )
    (net (code "33") (name "GPIO29") (class "Default")
      (node (ref "ADC") (pin "4") (pinfunction "4_4") (pintype "passive"))
      (node (ref "U1") (pin "41") (pinfunction "GPIO29/ADC3_41") (pintype "bidirectional"))
    )
    (net (code "34") (name "MCU_USB_DM") (class "Default")
      (node (ref "R2") (pin "2") (pinfunction "2_2") (pintype "passive"))
      (node (ref "U1") (pin "46") (pinfunction "USB_DM_46") (pintype "bidirectional"))
    )
    (net (code "35") (name "MCU_USB_DP") (class "Default")
      (node (ref "R1") (pin "2") (pinfunction "2_2") (pintype "passive"))
      (node (ref "U1") (pin "47") (pinfunction "USB_DP_47") (pintype "bidirectional"))
    )
    (net (code "36") (name "Net-(BOOTSEL-Pad1)") (class "Default")
      (node (ref "BOOTSEL") (pin "1") (pinfunction "1_1") (pintype "passive"))
      (node (ref "R4") (pin "2") (pinfunction "2_2") (pintype "passive"))
    )
    (net (code "37") (name "Net-(C13-Pad1)") (class "Default")
      (node (ref "C13") (pin "1") (pinfunction "1_1") (pintype "passive"))
      (node (ref "R12") (pin "2") (pinfunction "2_2") (pintype "passive"))
      (node (ref "Y1") (pin "3") (pinfunction "3_3") (pintype "passive"))
    )
    (net (code "38") (name "Net-(D1-C)") (class "Default")
      (node (ref "D1") (pin "1") (pinfunction "C_1") (pintype "passive"))
      (node (ref "D2") (pin "1") (pinfunction "C_1") (pintype "passive"))
      (node (ref "D3") (pin "1") (pinfunction "C_1") (pintype "passive"))
      (node (ref "D4") (pin "1") (pinfunction "C_1") (pintype "passive"))
      (node (ref "D5") (pin "1") (pinfunction "C_1") (pintype "passive"))
      (node (ref "R6") (pin "1") (pinfunction "1_1") (pintype "passive"))
    )
    (net (code "39") (name "Net-(D10-C)") (class "Default")
      (node (ref "D10") (pin "1") (pinfunction "C_1") (pintype "passive"))
      (node (ref "D6") (pin "1") (pinfunction "C_1") (pintype "passive"))
      (node (ref "D7") (pin "1") (pinfunction "C_1") (pintype "passive"))
      (node (ref "D8") (pin "1") (pinfunction "C_1") (pintype "passive"))
      (node (ref "D9") (pin "1") (pinfunction "C_1") (pintype "passive"))
      (node (ref "R8") (pin "1") (pinfunction "1_1") (pintype "passive"))
    )
    (net (code "40") (name "Net-(D11-C)") (class "Default")
      (node (ref "D11") (pin "1") (pinfunction "C_1") (pintype "passive"))
      (node (ref "D12") (pin "1") (pinfunction "C_1") (pintype "passive"))
      (node (ref "D13") (pin "1") (pinfunction "C_1") (pintype "passive"))
      (node (ref "D14") (pin "1") (pinfunction "C_1") (pintype "passive"))
      (node (ref "D15") (pin "1") (pinfunction "C_1") (pintype "passive"))
      (node (ref "R10") (pin "1") (pinfunction "1_1") (pintype "passive"))
    )
    (net (code "41") (name "Net-(D16-C)") (class "Default")
      (node (ref "D16") (pin "1") (pinfunction "C_1") (pintype "passive"))
      (node (ref "D17") (pin "1") (pinfunction "C_1") (pintype "passive"))
      (node (ref "D18") (pin "1") (pinfunction "C_1") (pintype "passive"))
      (node (ref "D19") (pin "1") (pinfunction "C_1") (pintype "passive"))
      (node (ref "D20") (pin "1") (pinfunction "C_1") (pintype "passive"))
      (node (ref "R14") (pin "1") (pinfunction "1_1") (pintype "passive"))
    )
    (net (code "42") (name "Net-(D21-C)") (class "Default")
      (node (ref "D21") (pin "1") (pinfunction "C_1") (pintype "passive"))
      (node (ref "D22") (pin "1") (pinfunction "C_1") (pintype "passive"))
      (node (ref "D23") (pin "1") (pinfunction "C_1") (pintype "passive"))
      (node (ref "D24") (pin "1") (pinfunction "C_1") (pintype "passive"))
      (node (ref "D25") (pin "1") (pinfunction "C_1") (pintype "passive"))
      (node (ref "R16") (pin "1") (pinfunction "1_1") (pintype "passive"))
    )
    (net (code "43") (name "Net-(R6-Pad2)") (class "Default")
      (node (ref "R6") (pin "2") (pinfunction "2_2") (pintype "passive"))
      (node (ref "R7") (pin "1") (pinfunction "1_1") (pintype "passive"))
    )
    (net (code "44") (name "Net-(R8-Pad2)") (class "Default")
      (node (ref "R8") (pin "2") (pinfunction "2_2") (pintype "passive"))
      (node (ref "R9") (pin "1") (pinfunction "1_1") (pintype "passive"))
    )
    (net (code "45") (name "Net-(R10-Pad2)") (class "Default")
      (node (ref "R10") (pin "2") (pinfunction "2_2") (pintype "passive"))
      (node (ref "R13") (pin "1") (pinfunction "1_1") (pintype "passive"))
    )
    (net (code "46") (name "Net-(R14-Pad2)") (class "Default")
      (node (ref "R14") (pin "2") (pinfunction "2_2") (pintype "passive"))
      (node (ref "R15") (pin "1") (pinfunction "1_1") (pintype "passive"))
    )
    (net (code "47") (name "Net-(R16-Pad2)") (class "Default")
      (node (ref "R16") (pin "2") (pinfunction "2_2") (pintype "passive"))
      (node (ref "R17") (pin "1") (pinfunction "1_1") (pintype "passive"))
    )
    (net (code "48") (name "QSPI_SCLK") (class "Default")
      (node (ref "U1") (pin "52") (pinfunction "QSPI_SCLK_52") (pintype "bidirectional"))
      (node (ref "U2") (pin "6") (pinfunction "CLK_6") (pintype "input"))
    )
    (net (code "49") (name "QSPI_SD0") (class "Default")
      (node (ref "U1") (pin "53") (pinfunction "QSPI_SD0_53") (pintype "bidirectional"))
      (node (ref "U2") (pin "5") (pinfunction "DI(IO0)_5") (pintype "bidirectional"))
    )
    (net (code "50") (name "QSPI_SD1") (class "Default")
      (node (ref "U1") (pin "55") (pinfunction "QSPI_SD1_55") (pintype "bidirectional"))
      (node (ref "U2") (pin "2") (pinfunction "DO(IO1)_2") (pintype "bidirectional"))
    )
    (net (code "51") (name "QSPI_SD2") (class "Default")
      (node (ref "U1") (pin "54") (pinfunction "QSPI_SD2_54") (pintype "bidirectional"))
      (node (ref "U2") (pin "3") (pinfunction "~{WP}(IO2)_3") (pintype "bidirectional"))
    )
    (net (code "52") (name "QSPI_SD3") (class "Default")
      (node (ref "U1") (pin "51") (pinfunction "QSPI_SD3_51") (pintype "bidirectional"))
      (node (ref "U2") (pin "7") (pinfunction "~{HOLD}/~{RESET}(~{IO}3~{)}_7") (pintype "bidirectional"))
    )
    (net (code "53") (name "QSPI_SS") (class "Default")
      (node (ref "R3") (pin "2") (pinfunction "2_2") (pintype "passive"))
      (node (ref "R4") (pin "1") (pinfunction "1_1") (pintype "passive"))
      (node (ref "U1") (pin "56") (pinfunction "QSPI_CSN_56") (pintype "bidirectional"))
      (node (ref "U2") (pin "1") (pinfunction "~{CS}_1") (pintype "input"))
    )
    (net (code "54") (name "SWCLK") (class "Default")
      (node (ref "DEBUG") (pin "1") (pinfunction "1_1") (pintype "passive"))
      (node (ref "U1") (pin "24") (pinfunction "SWCLK_24") (pintype "input"))
    )
    (net (code "55") (name "SWDIO") (class "Default")
      (node (ref "DEBUG") (pin "3") (pinfunction "3_3") (pintype "passive"))
      (node (ref "U1") (pin "25") (pinfunction "SWD_25") (pintype "bidirectional"))
    )
    (net (code "56") (name "USB_CC1") (class "Default")
      (node (ref "J1") (pin "A5") (pinfunction "CC1_A5") (pintype "bidirectional"))
      (node (ref "R5") (pin "2") (pinfunction "2_2") (pintype "passive"))
    )
    (net (code "57") (name "USB_CC2") (class "Default")
      (node (ref "J1") (pin "B5") (pinfunction "CC2_B5") (pintype "bidirectional"))
      (node (ref "R11") (pin "2") (pinfunction "2_2") (pintype "passive"))
    )
    (net (code "58") (name "USB_DM") (class "Default")
      (node (ref "J1") (pin "A7") (pinfunction "DN1_A7") (pintype "bidirectional"))
      (node (ref "J1") (pin "B7") (pinfunction "DN2_B7") (pintype "bidirectional"))
      (node (ref "R2") (pin "1") (pinfunction "1_1") (pintype "passive"))
    )
    (net (code "59") (name "USB_DP") (class "Default")
      (node (ref "J1") (pin "A6") (pinfunction "DP1_A6") (pintype "bidirectional"))
      (node (ref "J1") (pin "B6") (pinfunction "DP2_B6") (pintype "bidirectional"))
      (node (ref "R1") (pin "1") (pinfunction "1_1") (pintype "passive"))
    )
    (net (code "60") (name "VBus") (class "Default")
      (node (ref "C14") (pin "1") (pinfunction "1_1") (pintype "passive"))
      (node (ref "J1") (pin "A4_B9") (pinfunction "VBUS_A4_B9") (pintype "power_in"))
      (node (ref "J1") (pin "A9_B4") (pinfunction "VBUS_A9_B4") (pintype "power_in"))
      (node (ref "U3") (pin "3") (pinfunction "VIN_3") (pintype "input"))
    )
    (net (code "61") (name "XIN") (class "Default")
      (node (ref "C12") (pin "1") (pinfunction "1_1") (pintype "passive"))
      (node (ref "U1") (pin "20") (pinfunction "XIN_20") (pintype "input"))
      (node (ref "Y1") (pin "1") (pinfunction "1_1") (pintype "passive"))
    )
    (net (code "62") (name "XOUT") (class "Default")
      (node (ref "R12") (pin "1") (pinfunction "1_1") (pintype "passive"))
      (node (ref "U1") (pin "21") (pinfunction "XOUT_21") (pintype "output"))
    )
    (net (code "63") (name "unconnected-(J1-SBU1-PadA8)") (class "Default")
      (node (ref "J1") (pin "A8") (pinfunction "SBU1_A8") (pintype "bidirectional"))
    )
    (net (code "64") (name "unconnected-(J1-SBU2-PadB8)") (class "Default")
      (node (ref "J1") (pin "B8") (pinfunction "SBU2_B8") (pintype "bidirectional"))
    )
  )
)
